# SBH_Charger_USB_PD.net
KiCad netlist of a schematic drawn in Altium Designer
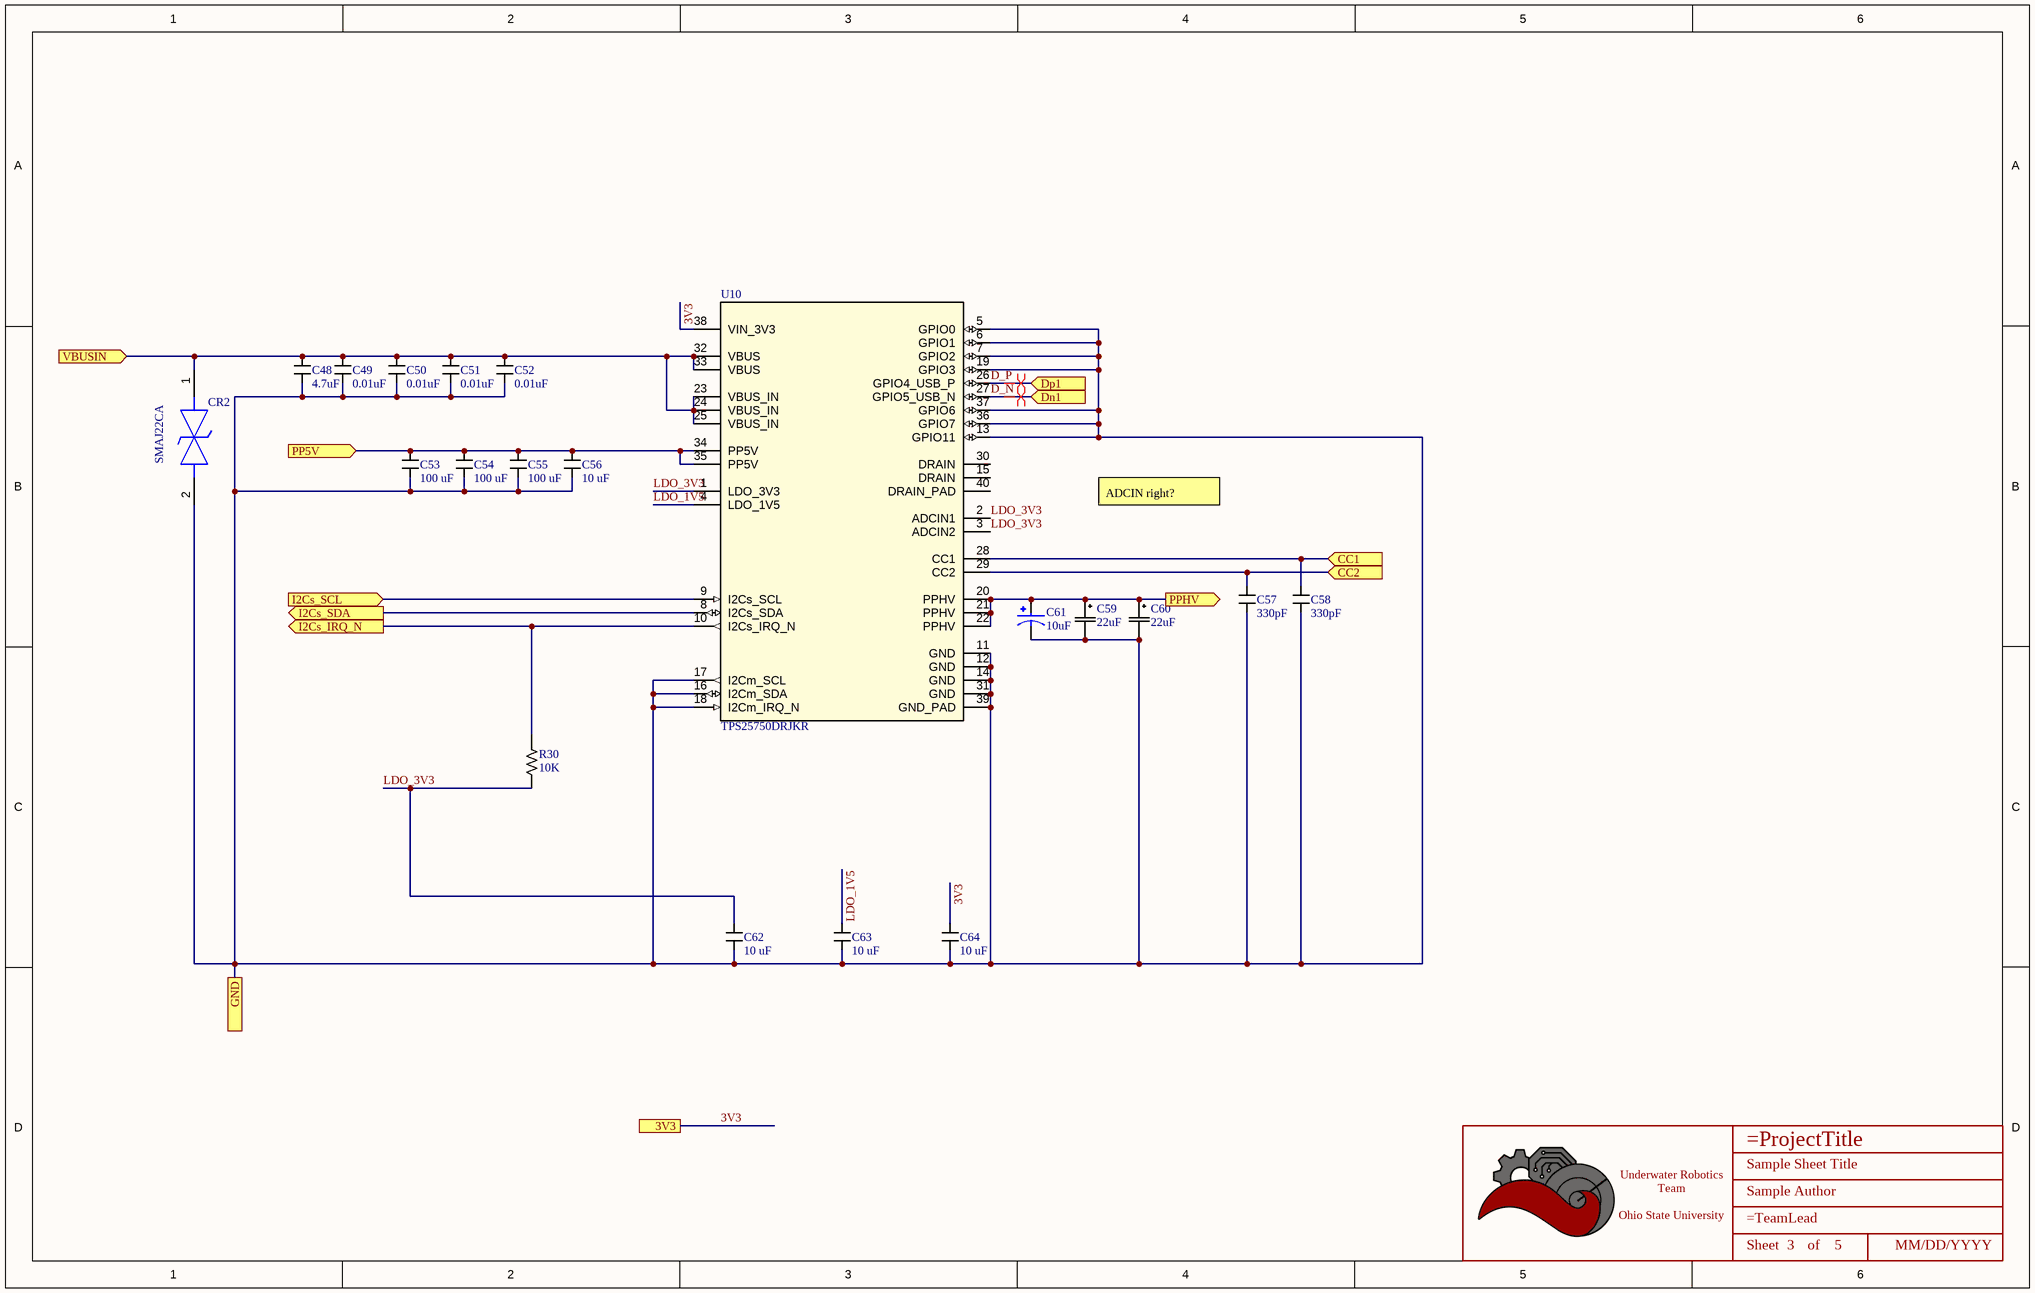
[diagram p0: SBH_Charger_USB_PD.SchDoc]

(export (version "E")
  (design (tool "Eeschema 10.0.6"))
  (components
    (comp (ref "*")
      (value "Title_Block")
      (footprint "LOGO")
      (description "UWRT Schematic Title Block Template\r\n\r\nCreated June 2021, Dylan Trainor")
      (libsource (lib "UWRT") (part "Title_Block"))
    )
    (comp (ref "C48")
      (value "4.7uF")
      (footprint "CAPACITOR_0603")
      (description "Cap 4.7uF 6.3V +/-10%\r\nCeramic 0603")
      (fields
        (field (name "TOLERANCE") "+/- 10%")
        (field (name "VOLTAGE") "6.3V")
        (field (name "MADE BY") "Robert Pafford")
      )
      (libsource (lib "Capacitors") (part "CAPACITOR_4.7uF_0603"))
    )
    (comp (ref "C49")
      (value "0.01uF")
      (footprint "CAPACITOR_0603")
      (description "Cap 10nF 6.3V +/-20%\r\nCeramic 0603")
      (fields
        (field (name "TOLERANCE") "+/- 10%")
        (field (name "VOLTAGE") "6.3V")
        (field (name "MADE BY") "Flip B")
      )
      (libsource (lib "Capacitors") (part "CAPACITOR_0.01uF_0603"))
    )
    (comp (ref "C50")
      (value "0.01uF")
      (footprint "CAPACITOR_0603")
      (description "Cap 10nF 6.3V +/-20%\r\nCeramic 0603")
      (fields
        (field (name "TOLERANCE") "+/- 10%")
        (field (name "VOLTAGE") "6.3V")
        (field (name "MADE BY") "Flip B")
      )
      (libsource (lib "Capacitors") (part "CAPACITOR_0.01uF_0603"))
    )
    (comp (ref "C51")
      (value "0.01uF")
      (footprint "CAPACITOR_0603")
      (description "Cap 10nF 6.3V +/-20%\r\nCeramic 0603")
      (fields
        (field (name "TOLERANCE") "+/- 10%")
        (field (name "VOLTAGE") "6.3V")
        (field (name "MADE BY") "Flip B")
      )
      (libsource (lib "Capacitors") (part "CAPACITOR_0.01uF_0603"))
    )
    (comp (ref "C52")
      (value "0.01uF")
      (footprint "CAPACITOR_0603")
      (description "Cap 10nF 6.3V +/-20%\r\nCeramic 0603")
      (fields
        (field (name "TOLERANCE") "+/- 10%")
        (field (name "VOLTAGE") "6.3V")
        (field (name "MADE BY") "Flip B")
      )
      (libsource (lib "Capacitors") (part "CAPACITOR_0.01uF_0603"))
    )
    (comp (ref "C53")
      (value "100uF Ceramic 6.3V")
      (footprint "CAPACITOR_0603")
      (description "Cap 100uF 6.3V +/-20%\r\nCeramic 0603")
      (fields
        (field (name "TOLERANCE") "+/- 20%")
        (field (name "VOLTAGE") "6.3V")
        (field (name "VALUE (UF)") "100 uF")
        (field (name "MADE BY") "Dylan Trainor")
      )
      (libsource (lib "Capacitors") (part "CAPACITOR_100uF_0603"))
    )
    (comp (ref "C54")
      (value "100uF Ceramic 6.3V")
      (footprint "CAPACITOR_0603")
      (description "Cap 100uF 6.3V +/-20%\r\nCeramic 0603")
      (fields
        (field (name "TOLERANCE") "+/- 20%")
        (field (name "VOLTAGE") "6.3V")
        (field (name "VALUE (UF)") "100 uF")
        (field (name "MADE BY") "Dylan Trainor")
      )
      (libsource (lib "Capacitors") (part "CAPACITOR_100uF_0603"))
    )
    (comp (ref "C55")
      (value "100uF Ceramic 6.3V")
      (footprint "CAPACITOR_0603")
      (description "Cap 100uF 6.3V +/-20%\r\nCeramic 0603")
      (fields
        (field (name "TOLERANCE") "+/- 20%")
        (field (name "VOLTAGE") "6.3V")
        (field (name "VALUE (UF)") "100 uF")
        (field (name "MADE BY") "Dylan Trainor")
      )
      (libsource (lib "Capacitors") (part "CAPACITOR_100uF_0603"))
    )
    (comp (ref "C56")
      (value "10uF Ceramic 6.3V")
      (footprint "CAPACITOR_0603")
      (description "Cap 10uF 6.3V +/-20%\r\nCeramic 0603")
      (fields
        (field (name "TOLERANCE") "+/- 20%")
        (field (name "VOLTAGE") "6.3V")
        (field (name "VALUE (UF)") "10 uF")
        (field (name "MADE BY") "Flip B")
      )
      (libsource (lib "Capacitors") (part "CAPACITOR_10uF_0603"))
    )
    (comp (ref "C57")
      (value "330pF")
      (footprint "CAPACITOR_0603")
      (description "Cap 330pF 16V +/-5%\r\nCeramic 0603")
      (fields
        (field (name "TOLERANCE") "+/- 5%")
        (field (name "VOLTAGE") "16V")
        (field (name "MADE BY") "Flip B")
      )
      (libsource (lib "Capacitors") (part "CAPACITOR_0.00033uF_0603"))
    )
    (comp (ref "C58")
      (value "330pF")
      (footprint "CAPACITOR_0603")
      (description "Cap 330pF 16V +/-5%\r\nCeramic 0603")
      (fields
        (field (name "TOLERANCE") "+/- 5%")
        (field (name "VOLTAGE") "16V")
        (field (name "MADE BY") "Flip B")
      )
      (libsource (lib "Capacitors") (part "CAPACITOR_0.00033uF_0603"))
    )
    (comp (ref "C59")
      (value "22uF")
      (footprint "PCAP_8x5.4-ELECT_NCA")
      (description "22 µF 35 V Aluminum Electrolytic Capacitors Radial, Can - SMD 1000 Hrs")
      (fields
        (field (name "VOLTAGE") "35V")
        (field (name "Comment") "22uF electrolytic 35 V")
        (field (name "MADE BY") "Robert Pafford")
      )
      (libsource (lib "Capacitors") (part "CAP ALUM 22UF 20% 35V SMD"))
    )
    (comp (ref "C60")
      (value "22uF")
      (footprint "PCAP_8x5.4-ELECT_NCA")
      (description "22 µF 35 V Aluminum Electrolytic Capacitors Radial, Can - SMD 1000 Hrs")
      (fields
        (field (name "VOLTAGE") "35V")
        (field (name "Comment") "22uF electrolytic 35 V")
        (field (name "MADE BY") "Robert Pafford")
      )
      (libsource (lib "Capacitors") (part "CAP ALUM 22UF 20% 35V SMD"))
    )
    (comp (ref "C61")
      (value "10uF")
      (footprint "CAP_EEHZC1J100P")
      (description "10 µF 63 V Aluminum - Polymer Capacitors Radial, Can SMD 120mOhm")
      (fields
        (field (name "TOLERANCE") "+/- 20%")
        (field (name "Comment") "10uF electrolytic 63V")
        (field (name "MADE BY") "Robert Pafford")
      )
      (libsource (lib "Capacitors") (part "CAP ALUM 10UF 20% 63V SMD"))
    )
    (comp (ref "C62")
      (value "10uF Ceramic 6.3V")
      (footprint "CAPACITOR_0603")
      (description "Cap 10uF 6.3V +/-20%\r\nCeramic 0603")
      (fields
        (field (name "TOLERANCE") "+/- 20%")
        (field (name "VOLTAGE") "6.3V")
        (field (name "VALUE (UF)") "10 uF")
        (field (name "MADE BY") "Flip B")
      )
      (libsource (lib "Capacitors") (part "CAPACITOR_10uF_0603"))
    )
    (comp (ref "C63")
      (value "10uF Ceramic 6.3V")
      (footprint "CAPACITOR_0603")
      (description "Cap 10uF 6.3V +/-20%\r\nCeramic 0603")
      (fields
        (field (name "TOLERANCE") "+/- 20%")
        (field (name "VOLTAGE") "6.3V")
        (field (name "VALUE (UF)") "10 uF")
        (field (name "MADE BY") "Flip B")
      )
      (libsource (lib "Capacitors") (part "CAPACITOR_10uF_0603"))
    )
    (comp (ref "C64")
      (value "10uF Ceramic 6.3V")
      (footprint "CAPACITOR_0603")
      (description "Cap 10uF 6.3V +/-20%\r\nCeramic 0603")
      (fields
        (field (name "TOLERANCE") "+/- 20%")
        (field (name "VOLTAGE") "6.3V")
        (field (name "VALUE (UF)") "10 uF")
        (field (name "MADE BY") "Flip B")
      )
      (libsource (lib "Capacitors") (part "CAPACITOR_10uF_0603"))
    )
    (comp (ref "CR2")
      (value "SMAJ22CA")
      (footprint "FP-SMAJ-CA-MFG")
      (description "TVS DIODE 22V 35.5V DO214AC")
      (libsource (lib "Altium Content Vault") (part "32812f50d15427265c9d073456c674c"))
    )
    (comp (ref "R30")
      (value "10k Ohm 1% 1/16W")
      (footprint "RESISTOR_0402")
      (description "RES 10k OHM 1% 1/16W 0402")
      (fields
        (field (name "TOLERANCE") "+/- 1%")
        (field (name "VALUE  (OHMS)") "10K")
        (field (name "MADE BY") "Robert Pafford")
      )
      (libsource (lib "Resistors") (part "RESISTOR_10K_0402"))
    )
    (comp (ref "U10")
      (value "TPS25750DRJKR")
      (footprint "38-WQFN (4x6)")
      (description "USB, Type-C Controller PMIC 38-WQFN (4x6)")
      (fields
        (field (name "COPYRIGHT") "Copyright (C) 2023 Ultra Librarian. All rights reserved.")
        (field (name "MADE BY") "Andrew Lin")
      )
      (libsource (lib "Integrated Circuits") (part "TPS25750DRJKR"))
    )
  )
  (nets
    (net (code "1") (name "/3V3") (class "Default")
      (node (ref "C64") (pin "1") (pinfunction "1_1") (pintype "passive"))
      (node (ref "U10") (pin "38") (pinfunction "VIN_3V3_38") (pintype "power_in"))
    )
    (net (code "2") (name "/CC1") (class "Default")
      (node (ref "C58") (pin "1") (pinfunction "1_1") (pintype "passive"))
      (node (ref "U10") (pin "28") (pinfunction "CC1_28") (pintype "passive"))
    )
    (net (code "3") (name "/CC2") (class "Default")
      (node (ref "C57") (pin "1") (pinfunction "1_1") (pintype "passive"))
      (node (ref "U10") (pin "29") (pinfunction "CC2_29") (pintype "passive"))
    )
    (net (code "4") (name "/D_N") (class "Default")
      (node (ref "U10") (pin "27") (pinfunction "GPIO5_USB_N_27") (pintype "bidirectional"))
    )
    (net (code "5") (name "/D_P") (class "Default")
      (node (ref "U10") (pin "26") (pinfunction "GPIO4_USB_P_26") (pintype "bidirectional"))
    )
    (net (code "6") (name "/GND") (class "Default")
      (node (ref "C48") (pin "2") (pinfunction "2_2") (pintype "passive"))
      (node (ref "C49") (pin "2") (pinfunction "2_2") (pintype "passive"))
      (node (ref "C50") (pin "2") (pinfunction "2_2") (pintype "passive"))
      (node (ref "C51") (pin "2") (pinfunction "2_2") (pintype "passive"))
      (node (ref "C52") (pin "2") (pinfunction "2_2") (pintype "passive"))
      (node (ref "C53") (pin "2") (pinfunction "2_2") (pintype "passive"))
      (node (ref "C54") (pin "2") (pinfunction "2_2") (pintype "passive"))
      (node (ref "C55") (pin "2") (pinfunction "2_2") (pintype "passive"))
      (node (ref "C56") (pin "2") (pinfunction "2_2") (pintype "passive"))
      (node (ref "C57") (pin "2") (pinfunction "2_2") (pintype "passive"))
      (node (ref "C58") (pin "2") (pinfunction "2_2") (pintype "passive"))
      (node (ref "C59") (pin "2") (pinfunction "2_2") (pintype "passive"))
      (node (ref "C60") (pin "2") (pinfunction "2_2") (pintype "passive"))
      (node (ref "C61") (pin "2") (pinfunction "2_2") (pintype "passive"))
      (node (ref "C62") (pin "2") (pinfunction "2_2") (pintype "passive"))
      (node (ref "C63") (pin "2") (pinfunction "2_2") (pintype "passive"))
      (node (ref "C64") (pin "2") (pinfunction "2_2") (pintype "passive"))
      (node (ref "CR2") (pin "2") (pinfunction "2_2") (pintype "passive"))
      (node (ref "U10") (pin "11") (pinfunction "GND_11") (pintype "power_in"))
      (node (ref "U10") (pin "12") (pinfunction "GND_12") (pintype "power_in"))
      (node (ref "U10") (pin "13") (pinfunction "GPIO11_13") (pintype "bidirectional"))
      (node (ref "U10") (pin "14") (pinfunction "GND_14") (pintype "power_in"))
      (node (ref "U10") (pin "16") (pinfunction "I2Cm_SDA_16") (pintype "bidirectional"))
      (node (ref "U10") (pin "17") (pinfunction "I2Cm_SCL_17") (pintype "output"))
      (node (ref "U10") (pin "18") (pinfunction "I2Cm_IRQ_N_18") (pintype "input"))
      (node (ref "U10") (pin "19") (pinfunction "GPIO3_19") (pintype "bidirectional"))
      (node (ref "U10") (pin "31") (pinfunction "GND_31") (pintype "power_in"))
      (node (ref "U10") (pin "36") (pinfunction "GPIO7_36") (pintype "bidirectional"))
      (node (ref "U10") (pin "37") (pinfunction "GPIO6_37") (pintype "bidirectional"))
      (node (ref "U10") (pin "39") (pinfunction "GND_PAD_39") (pintype "power_in"))
      (node (ref "U10") (pin "5") (pinfunction "GPIO0_5") (pintype "bidirectional"))
      (node (ref "U10") (pin "6") (pinfunction "GPIO1_6") (pintype "bidirectional"))
      (node (ref "U10") (pin "7") (pinfunction "GPIO2_7") (pintype "bidirectional"))
    )
    (net (code "7") (name "/I2Cs_IRQ_N") (class "Default")
      (node (ref "R30") (pin "1") (pinfunction "1_1") (pintype "passive"))
      (node (ref "U10") (pin "10") (pinfunction "I2Cs_IRQ_N_10") (pintype "output"))
    )
    (net (code "8") (name "/I2Cs_SCL") (class "Default")
      (node (ref "U10") (pin "9") (pinfunction "I2Cs_SCL_9") (pintype "input"))
    )
    (net (code "9") (name "/I2Cs_SDA") (class "Default")
      (node (ref "U10") (pin "8") (pinfunction "I2Cs_SDA_8") (pintype "bidirectional"))
    )
    (net (code "10") (name "/LDO_1V5") (class "Default")
      (node (ref "C63") (pin "1") (pinfunction "1_1") (pintype "passive"))
      (node (ref "U10") (pin "4") (pinfunction "LDO_1V5_4") (pintype "passive"))
    )
    (net (code "11") (name "/LDO_3V3") (class "Default")
      (node (ref "C62") (pin "1") (pinfunction "1_1") (pintype "passive"))
      (node (ref "R30") (pin "2") (pinfunction "2_2") (pintype "passive"))
      (node (ref "U10") (pin "1") (pinfunction "LDO_3V3_1") (pintype "passive"))
      (node (ref "U10") (pin "2") (pinfunction "ADCIN1_2") (pintype "passive"))
      (node (ref "U10") (pin "3") (pinfunction "ADCIN2_3") (pintype "passive"))
    )
    (net (code "12") (name "/PP5V") (class "Default")
      (node (ref "C53") (pin "1") (pinfunction "1_1") (pintype "passive"))
      (node (ref "C54") (pin "1") (pinfunction "1_1") (pintype "passive"))
      (node (ref "C55") (pin "1") (pinfunction "1_1") (pintype "passive"))
      (node (ref "C56") (pin "1") (pinfunction "1_1") (pintype "passive"))
      (node (ref "U10") (pin "34") (pinfunction "PP5V_34") (pintype "power_in"))
      (node (ref "U10") (pin "35") (pinfunction "PP5V_35") (pintype "power_in"))
    )
    (net (code "13") (name "/PPHV") (class "Default")
      (node (ref "C59") (pin "1") (pinfunction "1_1") (pintype "passive"))
      (node (ref "C60") (pin "1") (pinfunction "1_1") (pintype "passive"))
      (node (ref "C61") (pin "1") (pinfunction "1_1") (pintype "passive"))
      (node (ref "U10") (pin "20") (pinfunction "PPHV_20") (pintype "passive"))
      (node (ref "U10") (pin "21") (pinfunction "PPHV_21") (pintype "passive"))
      (node (ref "U10") (pin "22") (pinfunction "PPHV_22") (pintype "passive"))
    )
    (net (code "14") (name "/VBUSIN") (class "Default")
      (node (ref "C48") (pin "1") (pinfunction "1_1") (pintype "passive"))
      (node (ref "C49") (pin "1") (pinfunction "1_1") (pintype "passive"))
      (node (ref "C50") (pin "1") (pinfunction "1_1") (pintype "passive"))
      (node (ref "C51") (pin "1") (pinfunction "1_1") (pintype "passive"))
      (node (ref "C52") (pin "1") (pinfunction "1_1") (pintype "passive"))
      (node (ref "CR2") (pin "1") (pinfunction "1_1") (pintype "passive"))
      (node (ref "U10") (pin "23") (pinfunction "VBUS_IN_23") (pintype "power_in"))
      (node (ref "U10") (pin "24") (pinfunction "VBUS_IN_24") (pintype "power_in"))
      (node (ref "U10") (pin "25") (pinfunction "VBUS_IN_25") (pintype "power_in"))
      (node (ref "U10") (pin "32") (pinfunction "VBUS_32") (pintype "power_in"))
      (node (ref "U10") (pin "33") (pinfunction "VBUS_33") (pintype "power_in"))
    )
    (net (code "15") (name "unconnected-(U10-DRAIN-Pad15)") (class "Default")
      (node (ref "U10") (pin "15") (pinfunction "DRAIN_15") (pintype "passive"))
    )
    (net (code "16") (name "unconnected-(U10-DRAIN-Pad30)") (class "Default")
      (node (ref "U10") (pin "30") (pinfunction "DRAIN_30") (pintype "passive"))
    )
    (net (code "17") (name "unconnected-(U10-DRAIN_PAD-Pad40)") (class "Default")
      (node (ref "U10") (pin "40") (pinfunction "DRAIN_PAD_40") (pintype "passive"))
    )
  )
)
